# OPG_v8_schematics.net
KiCad netlist of a schematic drawn in Altium Designer
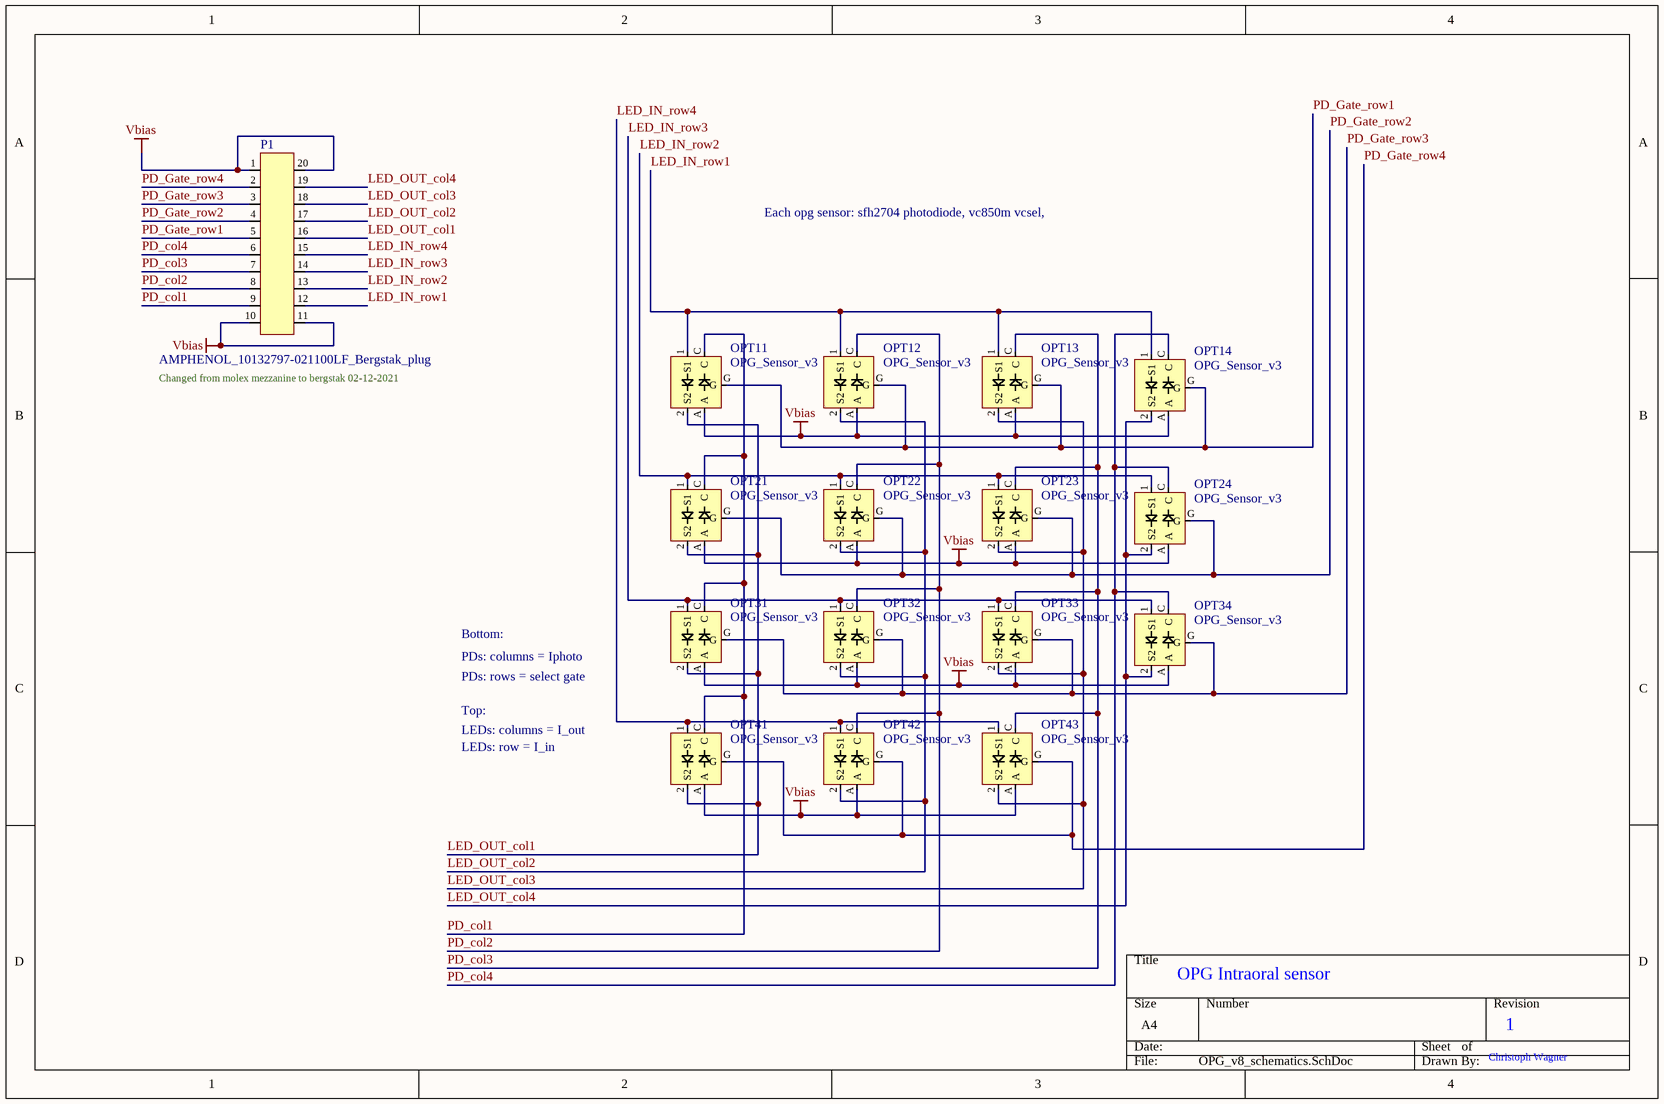
[diagram p0: OPG_v8_schematics.SchDoc]

(export (version "E")
  (design (tool "Eeschema 10.0.6"))
  (components
    (comp (ref "OPT11")
      (value "OPG_Sensor_v3")
      (footprint "OPG_SENSOR_3")
      (libsource (lib "LaserDiode") (part "OPG_Sensor_v3"))
    )
    (comp (ref "OPT12")
      (value "OPG_Sensor_v3")
      (footprint "OPG_SENSOR_3")
      (libsource (lib "LaserDiode") (part "OPG_Sensor_v3"))
    )
    (comp (ref "OPT13")
      (value "OPG_Sensor_v3")
      (footprint "OPG_SENSOR_3")
      (libsource (lib "LaserDiode") (part "OPG_Sensor_v3"))
    )
    (comp (ref "OPT14")
      (value "OPG_Sensor_v3")
      (footprint "OPG_SENSOR_3")
      (libsource (lib "LaserDiode") (part "OPG_Sensor_v3"))
    )
    (comp (ref "OPT21")
      (value "OPG_Sensor_v3")
      (footprint "OPG_SENSOR_3")
      (libsource (lib "LaserDiode") (part "OPG_Sensor_v3"))
    )
    (comp (ref "OPT22")
      (value "OPG_Sensor_v3")
      (footprint "OPG_SENSOR_3")
      (libsource (lib "LaserDiode") (part "OPG_Sensor_v3"))
    )
    (comp (ref "OPT23")
      (value "OPG_Sensor_v3")
      (footprint "OPG_SENSOR_3")
      (libsource (lib "LaserDiode") (part "OPG_Sensor_v3"))
    )
    (comp (ref "OPT24")
      (value "OPG_Sensor_v3")
      (footprint "OPG_SENSOR_3")
      (libsource (lib "LaserDiode") (part "OPG_Sensor_v3"))
    )
    (comp (ref "OPT31")
      (value "OPG_Sensor_v3")
      (footprint "OPG_SENSOR_3")
      (libsource (lib "LaserDiode") (part "OPG_Sensor_v3"))
    )
    (comp (ref "OPT32")
      (value "OPG_Sensor_v3")
      (footprint "OPG_SENSOR_3")
      (libsource (lib "LaserDiode") (part "OPG_Sensor_v3"))
    )
    (comp (ref "OPT33")
      (value "OPG_Sensor_v3")
      (footprint "OPG_SENSOR_3")
      (libsource (lib "LaserDiode") (part "OPG_Sensor_v3"))
    )
    (comp (ref "OPT34")
      (value "OPG_Sensor_v3")
      (footprint "OPG_SENSOR_3")
      (libsource (lib "LaserDiode") (part "OPG_Sensor_v3"))
    )
    (comp (ref "OPT41")
      (value "OPG_Sensor_v3")
      (footprint "OPG_SENSOR_3")
      (libsource (lib "LaserDiode") (part "OPG_Sensor_v3"))
    )
    (comp (ref "OPT42")
      (value "OPG_Sensor_v3")
      (footprint "OPG_SENSOR_3")
      (libsource (lib "LaserDiode") (part "OPG_Sensor_v3"))
    )
    (comp (ref "OPT43")
      (value "OPG_Sensor_v3")
      (footprint "OPG_SENSOR_3")
      (libsource (lib "LaserDiode") (part "OPG_Sensor_v3"))
    )
    (comp (ref "P1")
      (value "AMPHENOL_10132797-021100LF_Bergstak_plug")
      (footprint "AMPHENOL_10132797-021100LF_Bergstak_plug")
      (description "20 pin, 0.5 mm pitch, 3 mm mated height, plug/male")
      (libsource (lib "Connectors") (part "AMPHENOL_10132797-021100LF_Bergstak_plug"))
    )
  )
  (nets
    (net (code "1") (name "/LED_IN_row1") (class "Default")
      (node (ref "OPT11") (pin "1") (pinfunction "S1_1") (pintype "passive"))
      (node (ref "OPT12") (pin "1") (pinfunction "S1_1") (pintype "passive"))
      (node (ref "OPT13") (pin "1") (pinfunction "S1_1") (pintype "passive"))
      (node (ref "OPT14") (pin "1") (pinfunction "S1_1") (pintype "passive"))
      (node (ref "P1") (pin "12") (pintype "passive"))
    )
    (net (code "2") (name "/LED_IN_row2") (class "Default")
      (node (ref "OPT21") (pin "1") (pinfunction "S1_1") (pintype "passive"))
      (node (ref "OPT22") (pin "1") (pinfunction "S1_1") (pintype "passive"))
      (node (ref "OPT23") (pin "1") (pinfunction "S1_1") (pintype "passive"))
      (node (ref "OPT24") (pin "1") (pinfunction "S1_1") (pintype "passive"))
      (node (ref "P1") (pin "13") (pintype "passive"))
    )
    (net (code "3") (name "/LED_IN_row3") (class "Default")
      (node (ref "OPT31") (pin "1") (pinfunction "S1_1") (pintype "passive"))
      (node (ref "OPT32") (pin "1") (pinfunction "S1_1") (pintype "passive"))
      (node (ref "OPT33") (pin "1") (pinfunction "S1_1") (pintype "passive"))
      (node (ref "OPT34") (pin "1") (pinfunction "S1_1") (pintype "passive"))
      (node (ref "P1") (pin "14") (pintype "passive"))
    )
    (net (code "4") (name "/LED_IN_row4") (class "Default")
      (node (ref "OPT41") (pin "1") (pinfunction "S1_1") (pintype "passive"))
      (node (ref "OPT42") (pin "1") (pinfunction "S1_1") (pintype "passive"))
      (node (ref "OPT43") (pin "1") (pinfunction "S1_1") (pintype "passive"))
      (node (ref "P1") (pin "15") (pintype "passive"))
    )
    (net (code "5") (name "/LED_OUT_col1") (class "Default")
      (node (ref "OPT11") (pin "2") (pinfunction "S2_2") (pintype "passive"))
      (node (ref "OPT21") (pin "2") (pinfunction "S2_2") (pintype "passive"))
      (node (ref "OPT31") (pin "2") (pinfunction "S2_2") (pintype "passive"))
      (node (ref "OPT41") (pin "2") (pinfunction "S2_2") (pintype "passive"))
      (node (ref "P1") (pin "16") (pintype "passive"))
    )
    (net (code "6") (name "/LED_OUT_col2") (class "Default")
      (node (ref "OPT12") (pin "2") (pinfunction "S2_2") (pintype "passive"))
      (node (ref "OPT22") (pin "2") (pinfunction "S2_2") (pintype "passive"))
      (node (ref "OPT32") (pin "2") (pinfunction "S2_2") (pintype "passive"))
      (node (ref "OPT42") (pin "2") (pinfunction "S2_2") (pintype "passive"))
      (node (ref "P1") (pin "17") (pintype "passive"))
    )
    (net (code "7") (name "/LED_OUT_col3") (class "Default")
      (node (ref "OPT13") (pin "2") (pinfunction "S2_2") (pintype "passive"))
      (node (ref "OPT23") (pin "2") (pinfunction "S2_2") (pintype "passive"))
      (node (ref "OPT33") (pin "2") (pinfunction "S2_2") (pintype "passive"))
      (node (ref "OPT43") (pin "2") (pinfunction "S2_2") (pintype "passive"))
      (node (ref "P1") (pin "18") (pintype "passive"))
    )
    (net (code "8") (name "/LED_OUT_col4") (class "Default")
      (node (ref "OPT14") (pin "2") (pinfunction "S2_2") (pintype "passive"))
      (node (ref "OPT24") (pin "2") (pinfunction "S2_2") (pintype "passive"))
      (node (ref "OPT34") (pin "2") (pinfunction "S2_2") (pintype "passive"))
      (node (ref "P1") (pin "19") (pintype "passive"))
    )
    (net (code "9") (name "/PD_Gate_row1") (class "Default")
      (node (ref "OPT11") (pin "G") (pinfunction "G_G") (pintype "passive"))
      (node (ref "OPT12") (pin "G") (pinfunction "G_G") (pintype "passive"))
      (node (ref "OPT13") (pin "G") (pinfunction "G_G") (pintype "passive"))
      (node (ref "OPT14") (pin "G") (pinfunction "G_G") (pintype "passive"))
      (node (ref "P1") (pin "5") (pintype "passive"))
    )
    (net (code "10") (name "/PD_Gate_row2") (class "Default")
      (node (ref "OPT21") (pin "G") (pinfunction "G_G") (pintype "passive"))
      (node (ref "OPT22") (pin "G") (pinfunction "G_G") (pintype "passive"))
      (node (ref "OPT23") (pin "G") (pinfunction "G_G") (pintype "passive"))
      (node (ref "OPT24") (pin "G") (pinfunction "G_G") (pintype "passive"))
      (node (ref "P1") (pin "4") (pintype "passive"))
    )
    (net (code "11") (name "/PD_Gate_row3") (class "Default")
      (node (ref "OPT31") (pin "G") (pinfunction "G_G") (pintype "passive"))
      (node (ref "OPT32") (pin "G") (pinfunction "G_G") (pintype "passive"))
      (node (ref "OPT33") (pin "G") (pinfunction "G_G") (pintype "passive"))
      (node (ref "OPT34") (pin "G") (pinfunction "G_G") (pintype "passive"))
      (node (ref "P1") (pin "3") (pintype "passive"))
    )
    (net (code "12") (name "/PD_Gate_row4") (class "Default")
      (node (ref "OPT41") (pin "G") (pinfunction "G_G") (pintype "passive"))
      (node (ref "OPT42") (pin "G") (pinfunction "G_G") (pintype "passive"))
      (node (ref "OPT43") (pin "G") (pinfunction "G_G") (pintype "passive"))
      (node (ref "P1") (pin "2") (pintype "passive"))
    )
    (net (code "13") (name "/PD_col1") (class "Default")
      (node (ref "OPT11") (pin "C") (pinfunction "C_C") (pintype "passive"))
      (node (ref "OPT21") (pin "C") (pinfunction "C_C") (pintype "passive"))
      (node (ref "OPT31") (pin "C") (pinfunction "C_C") (pintype "passive"))
      (node (ref "OPT41") (pin "C") (pinfunction "C_C") (pintype "passive"))
      (node (ref "P1") (pin "9") (pintype "passive"))
    )
    (net (code "14") (name "/PD_col2") (class "Default")
      (node (ref "OPT12") (pin "C") (pinfunction "C_C") (pintype "passive"))
      (node (ref "OPT22") (pin "C") (pinfunction "C_C") (pintype "passive"))
      (node (ref "OPT32") (pin "C") (pinfunction "C_C") (pintype "passive"))
      (node (ref "OPT42") (pin "C") (pinfunction "C_C") (pintype "passive"))
      (node (ref "P1") (pin "8") (pintype "passive"))
    )
    (net (code "15") (name "/PD_col3") (class "Default")
      (node (ref "OPT13") (pin "C") (pinfunction "C_C") (pintype "passive"))
      (node (ref "OPT23") (pin "C") (pinfunction "C_C") (pintype "passive"))
      (node (ref "OPT33") (pin "C") (pinfunction "C_C") (pintype "passive"))
      (node (ref "OPT43") (pin "C") (pinfunction "C_C") (pintype "passive"))
      (node (ref "P1") (pin "7") (pintype "passive"))
    )
    (net (code "16") (name "/PD_col4") (class "Default")
      (node (ref "OPT14") (pin "C") (pinfunction "C_C") (pintype "passive"))
      (node (ref "OPT24") (pin "C") (pinfunction "C_C") (pintype "passive"))
      (node (ref "OPT34") (pin "C") (pinfunction "C_C") (pintype "passive"))
      (node (ref "P1") (pin "6") (pintype "passive"))
    )
    (net (code "17") (name "Vbias") (class "Default")
      (node (ref "OPT11") (pin "A") (pinfunction "A_A") (pintype "passive"))
      (node (ref "OPT12") (pin "A") (pinfunction "A_A") (pintype "passive"))
      (node (ref "OPT13") (pin "A") (pinfunction "A_A") (pintype "passive"))
      (node (ref "OPT14") (pin "A") (pinfunction "A_A") (pintype "passive"))
      (node (ref "OPT21") (pin "A") (pinfunction "A_A") (pintype "passive"))
      (node (ref "OPT22") (pin "A") (pinfunction "A_A") (pintype "passive"))
      (node (ref "OPT23") (pin "A") (pinfunction "A_A") (pintype "passive"))
      (node (ref "OPT24") (pin "A") (pinfunction "A_A") (pintype "passive"))
      (node (ref "OPT31") (pin "A") (pinfunction "A_A") (pintype "passive"))
      (node (ref "OPT32") (pin "A") (pinfunction "A_A") (pintype "passive"))
      (node (ref "OPT33") (pin "A") (pinfunction "A_A") (pintype "passive"))
      (node (ref "OPT34") (pin "A") (pinfunction "A_A") (pintype "passive"))
      (node (ref "OPT41") (pin "A") (pinfunction "A_A") (pintype "passive"))
      (node (ref "OPT42") (pin "A") (pinfunction "A_A") (pintype "passive"))
      (node (ref "OPT43") (pin "A") (pinfunction "A_A") (pintype "passive"))
      (node (ref "P1") (pin "1") (pintype "passive"))
      (node (ref "P1") (pin "10") (pintype "passive"))
      (node (ref "P1") (pin "11") (pintype "passive"))
      (node (ref "P1") (pin "20") (pintype "passive"))
    )
  )
)
